# FPGA_01.net
KiCad netlist of a schematic drawn in Altium Designer
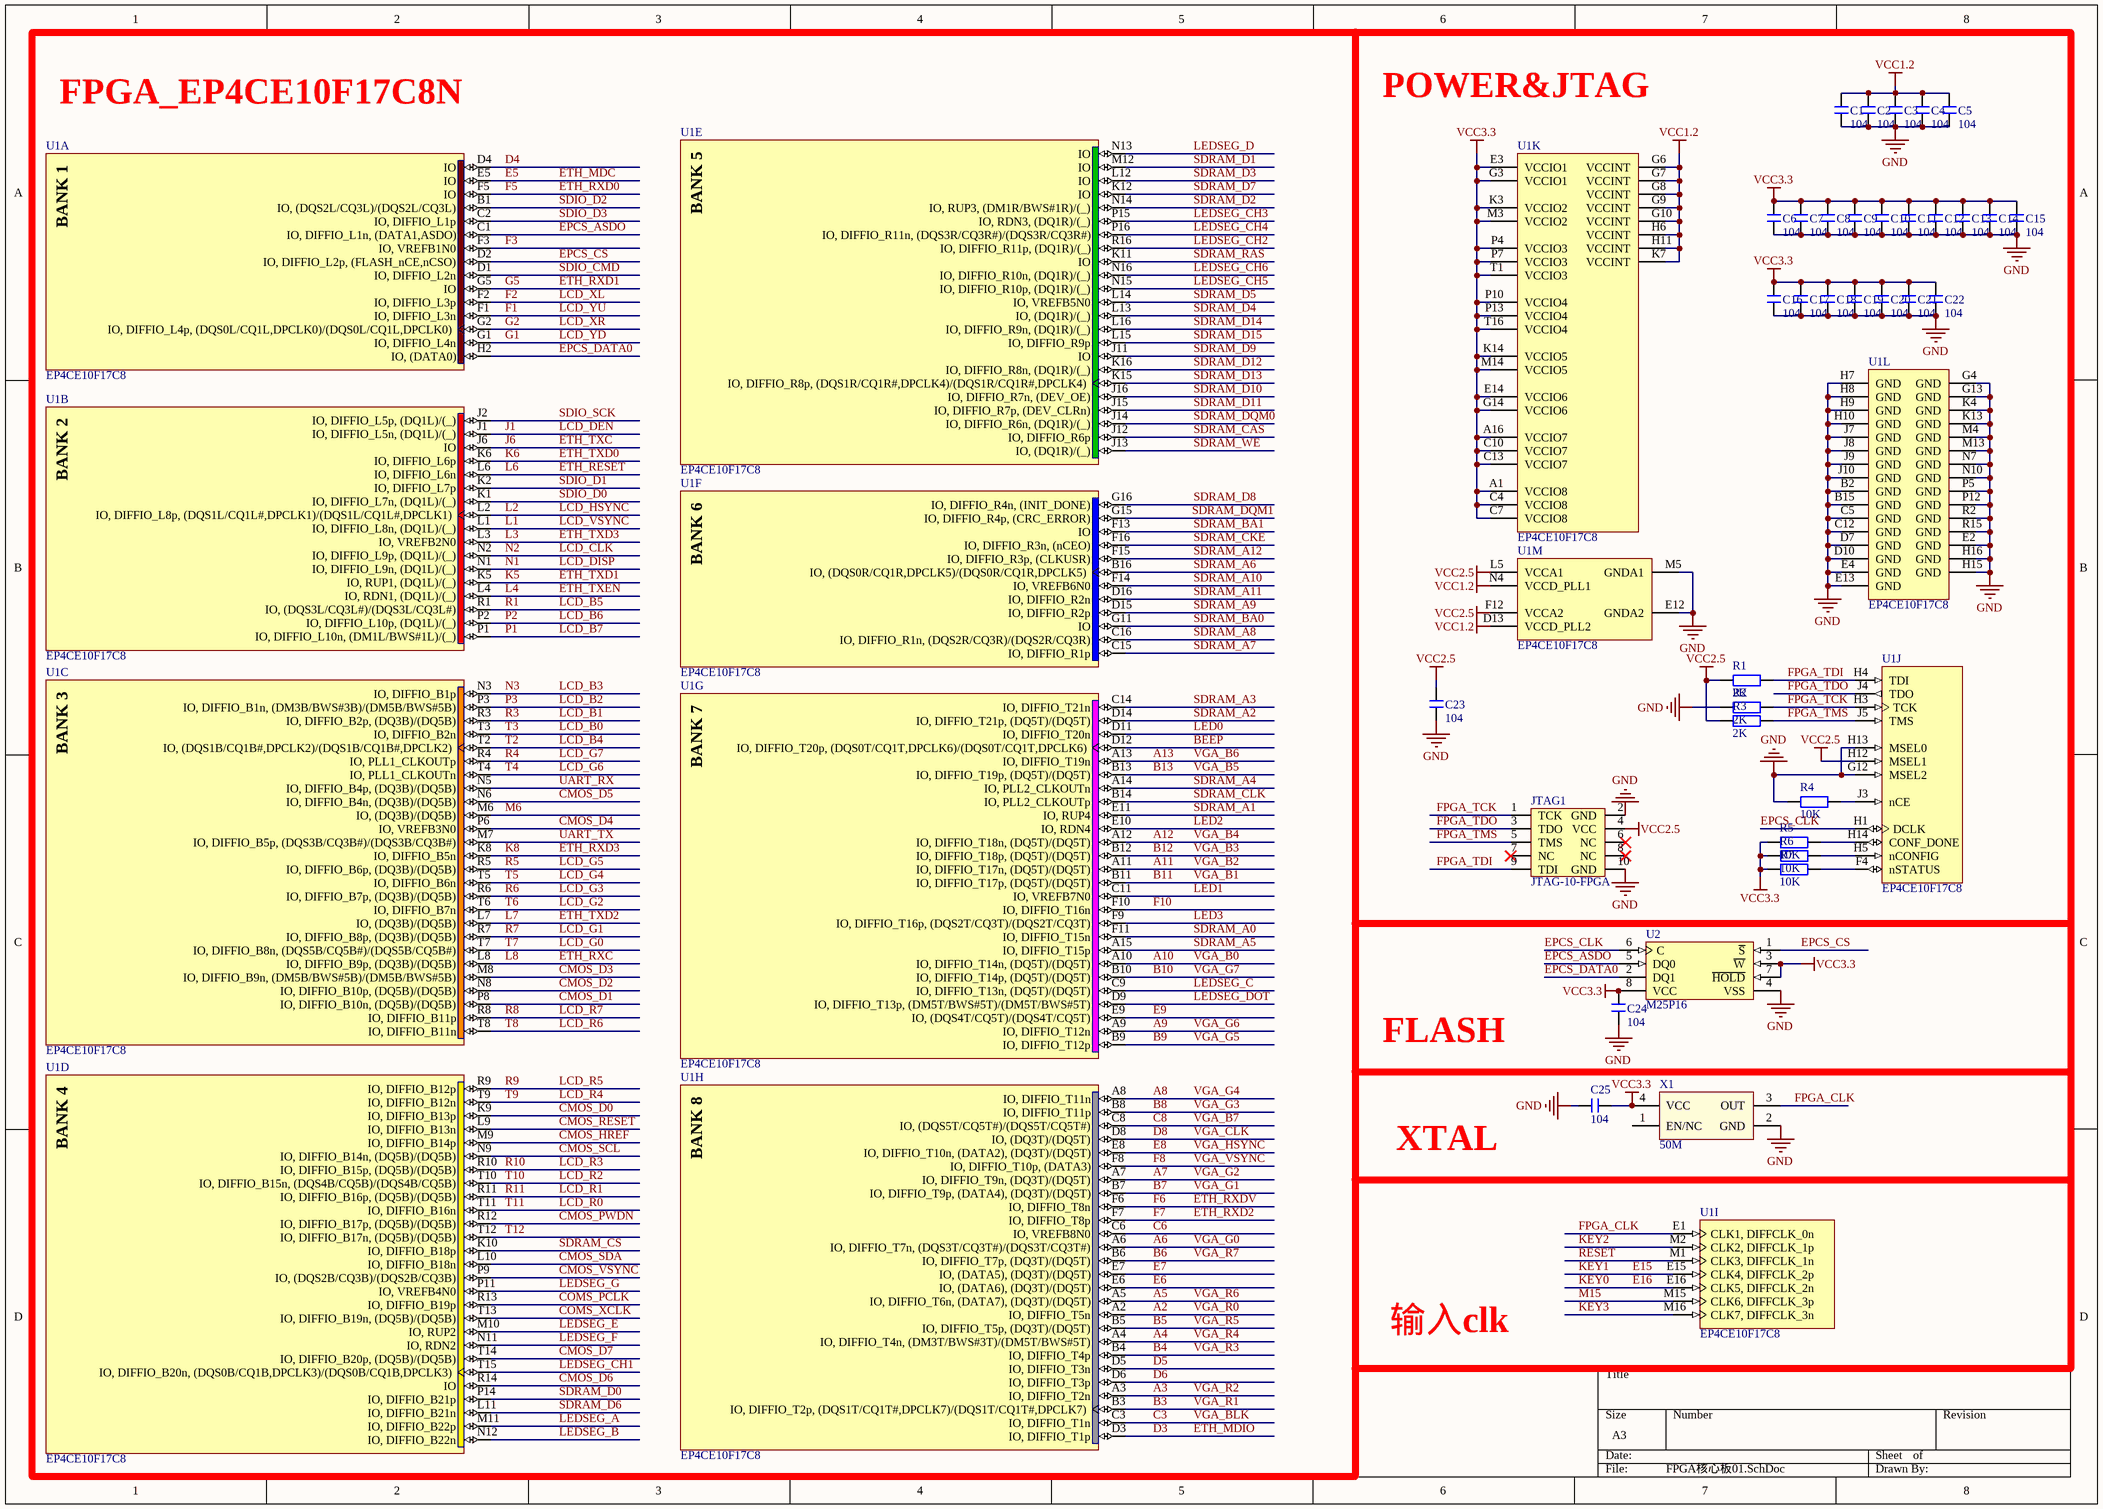
[diagram p0: FPGA核心板01.SchDoc]

(export (version "E")
  (design (tool "Eeschema 10.0.6"))
  (components
    (comp (ref "C1")
      (value "104")
      (footprint "C 0603_L")
      (description "贴片电容")
      (libsource (lib "0.1 - 电阻-电容-电感") (part "C"))
    )
    (comp (ref "C2")
      (value "104")
      (footprint "C 0603_L")
      (description "贴片电容")
      (libsource (lib "0.1 - 电阻-电容-电感") (part "C"))
    )
    (comp (ref "C3")
      (value "104")
      (footprint "C 0603_L")
      (description "贴片电容")
      (libsource (lib "0.1 - 电阻-电容-电感") (part "C"))
    )
    (comp (ref "C4")
      (value "104")
      (footprint "C 0603_L")
      (description "贴片电容")
      (libsource (lib "0.1 - 电阻-电容-电感") (part "C"))
    )
    (comp (ref "C5")
      (value "104")
      (footprint "C 0603_L")
      (description "贴片电容")
      (libsource (lib "0.1 - 电阻-电容-电感") (part "C"))
    )
    (comp (ref "C6")
      (value "104")
      (footprint "C 0603_L")
      (description "贴片电容")
      (libsource (lib "0.1 - 电阻-电容-电感") (part "C"))
    )
    (comp (ref "C7")
      (value "104")
      (footprint "C 0603_L")
      (description "贴片电容")
      (libsource (lib "0.1 - 电阻-电容-电感") (part "C"))
    )
    (comp (ref "C8")
      (value "104")
      (footprint "C 0603_L")
      (description "贴片电容")
      (libsource (lib "0.1 - 电阻-电容-电感") (part "C"))
    )
    (comp (ref "C9")
      (value "104")
      (footprint "C 0603_L")
      (description "贴片电容")
      (libsource (lib "0.1 - 电阻-电容-电感") (part "C"))
    )
    (comp (ref "C10")
      (value "104")
      (footprint "C 0603_L")
      (description "贴片电容")
      (libsource (lib "0.1 - 电阻-电容-电感") (part "C"))
    )
    (comp (ref "C11")
      (value "104")
      (footprint "C 0603_L")
      (description "贴片电容")
      (libsource (lib "0.1 - 电阻-电容-电感") (part "C"))
    )
    (comp (ref "C12")
      (value "104")
      (footprint "C 0603_L")
      (description "贴片电容")
      (libsource (lib "0.1 - 电阻-电容-电感") (part "C"))
    )
    (comp (ref "C13")
      (value "104")
      (footprint "C 0603_L")
      (description "贴片电容")
      (libsource (lib "0.1 - 电阻-电容-电感") (part "C"))
    )
    (comp (ref "C14")
      (value "104")
      (footprint "C 0603_L")
      (description "贴片电容")
      (libsource (lib "0.1 - 电阻-电容-电感") (part "C"))
    )
    (comp (ref "C15")
      (value "104")
      (footprint "C 0603_L")
      (description "贴片电容")
      (libsource (lib "0.1 - 电阻-电容-电感") (part "C"))
    )
    (comp (ref "C16")
      (value "104")
      (footprint "C 0603_L")
      (description "贴片电容")
      (libsource (lib "0.1 - 电阻-电容-电感") (part "C"))
    )
    (comp (ref "C17")
      (value "104")
      (footprint "C 0603_L")
      (description "贴片电容")
      (libsource (lib "0.1 - 电阻-电容-电感") (part "C"))
    )
    (comp (ref "C18")
      (value "104")
      (footprint "C 0603_L")
      (description "贴片电容")
      (libsource (lib "0.1 - 电阻-电容-电感") (part "C"))
    )
    (comp (ref "C19")
      (value "104")
      (footprint "C 0603_L")
      (description "贴片电容")
      (libsource (lib "0.1 - 电阻-电容-电感") (part "C"))
    )
    (comp (ref "C20")
      (value "104")
      (footprint "C 0603_L")
      (description "贴片电容")
      (libsource (lib "0.1 - 电阻-电容-电感") (part "C"))
    )
    (comp (ref "C21")
      (value "104")
      (footprint "C 0603_L")
      (description "贴片电容")
      (libsource (lib "0.1 - 电阻-电容-电感") (part "C"))
    )
    (comp (ref "C22")
      (value "104")
      (footprint "C 0603_L")
      (description "贴片电容")
      (libsource (lib "0.1 - 电阻-电容-电感") (part "C"))
    )
    (comp (ref "C23")
      (value "104")
      (footprint "C 0603_L")
      (description "贴片电容")
      (libsource (lib "0.1 - 电阻-电容-电感") (part "C"))
    )
    (comp (ref "C24")
      (value "104")
      (footprint "C 0603_L")
      (description "贴片电容")
      (libsource (lib "0.1 - 电阻-电容-电感") (part "C"))
    )
    (comp (ref "C25")
      (value "104")
      (footprint "C 0603_L")
      (description "贴片电容")
      (libsource (lib "0.1 - 电阻-电容-电感") (part "C"))
    )
    (comp (ref "JTAG1")
      (value "JTAG-10-FPGA")
      (footprint "JTAG_10_2.54")
      (libsource (lib "PIONEER") (part "JTAG-10-FPGA"))
    )
    (comp (ref "R1")
      (value "2K")
      (footprint "R 0603_L")
      (description "贴片电阻")
      (fields (field (name "版权归属") "来自淘宝 ID：黄晶宝石"))
      (libsource (lib "0.1 - 电阻-电容-电感") (part "R"))
    )
    (comp (ref "R2")
      (value "2K")
      (footprint "R 0603_L")
      (description "贴片电阻")
      (fields (field (name "版权归属") "来自淘宝 ID：黄晶宝石"))
      (libsource (lib "0.1 - 电阻-电容-电感") (part "R"))
    )
    (comp (ref "R3")
      (value "2K")
      (footprint "R 0603_L")
      (description "贴片电阻")
      (fields (field (name "版权归属") "来自淘宝 ID：黄晶宝石"))
      (libsource (lib "0.1 - 电阻-电容-电感") (part "R"))
    )
    (comp (ref "R4")
      (value "10K")
      (footprint "R 0603_L")
      (description "贴片电阻")
      (fields (field (name "版权归属") "来自淘宝 ID：黄晶宝石"))
      (libsource (lib "0.1 - 电阻-电容-电感") (part "R"))
    )
    (comp (ref "R5")
      (value "10K")
      (footprint "R 0603_L")
      (description "贴片电阻")
      (fields (field (name "版权归属") "来自淘宝 ID：黄晶宝石"))
      (libsource (lib "0.1 - 电阻-电容-电感") (part "R"))
    )
    (comp (ref "R6")
      (value "10K")
      (footprint "R 0603_L")
      (description "贴片电阻")
      (fields (field (name "版权归属") "来自淘宝 ID：黄晶宝石"))
      (libsource (lib "0.1 - 电阻-电容-电感") (part "R"))
    )
    (comp (ref "R7")
      (value "10K")
      (footprint "R 0603_L")
      (description "贴片电阻")
      (fields (field (name "版权归属") "来自淘宝 ID：黄晶宝石"))
      (libsource (lib "0.1 - 电阻-电容-电感") (part "R"))
    )
    (comp (ref "U1")
      (value "EP4CE10F17C8")
      (footprint "FBGA256")
      (fields (field (name "PUBLISHER") "Altium Limited"))
      (libsource (lib "PIONEER") (part "EP4CE6F17C8"))
    )
    (comp (ref "U2")
      (value "M25P16")
      (footprint "sop-8")
      (description "16 Mb (x1) Automotive Serial NOR Flash Memory, 75 MHz, 2.7 to 3.6 V, 8-pin SO8")
      (fields (field (name "VOLTAGE") "2.7V-3.6V爭ISHIDDEN=T¦") (field (name "MANUFACTURER") "Micron"))
      (libsource (lib "PIONEER") (part "M25P16"))
    )
    (comp (ref "X1")
      (value "50M")
      (footprint "OSC 3225-4P")
      (description "4脚有源晶振")
      (fields (field (name "版权归属") "源创客"))
      (libsource (lib "2.0 - 保险丝-晶振-光耦") (part "XTAL-ACT-4P"))
    )
  )
  (nets
    (net (code "1") (name "/A2") (class "Default")
      (node (ref "U1") (pin "A2") (pinfunction "IO,_DIFFIO_T5n_A2") (pintype "bidirectional"))
    )
    (net (code "2") (name "/A3") (class "Default")
      (node (ref "U1") (pin "A3") (pinfunction "IO,_DIFFIO_T2n_A3") (pintype "bidirectional"))
    )
    (net (code "3") (name "/A4") (class "Default")
      (node (ref "U1") (pin "A4") (pinfunction "IO,_DIFFIO_T4n,_(DM3T/BWS#3T)/(DM5T/BWS#5T)_A4") (pintype "bidirectional"))
    )
    (net (code "4") (name "/A5") (class "Default")
      (node (ref "U1") (pin "A5") (pinfunction "IO,_DIFFIO_T6n,_(DATA7),_(DQ3T)/(DQ5T)_A5") (pintype "bidirectional"))
    )
    (net (code "5") (name "/A6") (class "Default")
      (node (ref "U1") (pin "A6") (pinfunction "IO,_DIFFIO_T7n,_(DQS3T/CQ3T#)/(DQS3T/CQ3T#)_A6") (pintype "bidirectional"))
    )
    (net (code "6") (name "/A7") (class "Default")
      (node (ref "U1") (pin "A7") (pinfunction "IO,_DIFFIO_T9n,_(DQ3T)/(DQ5T)_A7") (pintype "bidirectional"))
    )
    (net (code "7") (name "/A8") (class "Default")
      (node (ref "U1") (pin "A8") (pinfunction "IO,_DIFFIO_T11n_A8") (pintype "bidirectional"))
    )
    (net (code "8") (name "/A9") (class "Default")
      (node (ref "U1") (pin "A9") (pinfunction "IO,_DIFFIO_T12n_A9") (pintype "bidirectional"))
    )
    (net (code "9") (name "/A10") (class "Default")
      (node (ref "U1") (pin "A10") (pinfunction "IO,_DIFFIO_T14n,_(DQ5T)/(DQ5T)_A10") (pintype "bidirectional"))
    )
    (net (code "10") (name "/A11") (class "Default")
      (node (ref "U1") (pin "A11") (pinfunction "IO,_DIFFIO_T17n,_(DQ5T)/(DQ5T)_A11") (pintype "bidirectional"))
    )
    (net (code "11") (name "/A12") (class "Default")
      (node (ref "U1") (pin "A12") (pinfunction "IO,_DIFFIO_T18n,_(DQ5T)/(DQ5T)_A12") (pintype "bidirectional"))
    )
    (net (code "12") (name "/A13") (class "Default")
      (node (ref "U1") (pin "A13") (pinfunction "IO,_DIFFIO_T19n_A13") (pintype "bidirectional"))
    )
    (net (code "13") (name "/B3") (class "Default")
      (node (ref "U1") (pin "B3") (pinfunction "IO,_DIFFIO_T2p,_(DQS1T/CQ1T#,DPCLK7)/(DQS1T/CQ1T#,DPCLK7)_B3") (pintype "bidirectional"))
    )
    (net (code "14") (name "/B4") (class "Default")
      (node (ref "U1") (pin "B4") (pinfunction "IO,_DIFFIO_T4p_B4") (pintype "bidirectional"))
    )
    (net (code "15") (name "/B5") (class "Default")
      (node (ref "U1") (pin "B5") (pinfunction "IO,_DIFFIO_T5p,_(DQ3T)/(DQ5T)_B5") (pintype "bidirectional"))
    )
    (net (code "16") (name "/B6") (class "Default")
      (node (ref "U1") (pin "B6") (pinfunction "IO,_DIFFIO_T7p,_(DQ3T)/(DQ5T)_B6") (pintype "bidirectional"))
    )
    (net (code "17") (name "/B7") (class "Default")
      (node (ref "U1") (pin "B7") (pinfunction "IO,_DIFFIO_T9p,_(DATA4),_(DQ3T)/(DQ5T)_B7") (pintype "bidirectional"))
    )
    (net (code "18") (name "/B8") (class "Default")
      (node (ref "U1") (pin "B8") (pinfunction "IO,_DIFFIO_T11p_B8") (pintype "bidirectional"))
    )
    (net (code "19") (name "/B9") (class "Default")
      (node (ref "U1") (pin "B9") (pinfunction "IO,_DIFFIO_T12p_B9") (pintype "bidirectional"))
    )
    (net (code "20") (name "/B10") (class "Default")
      (node (ref "U1") (pin "B10") (pinfunction "IO,_DIFFIO_T14p,_(DQ5T)/(DQ5T)_B10") (pintype "bidirectional"))
    )
    (net (code "21") (name "/B11") (class "Default")
      (node (ref "U1") (pin "B11") (pinfunction "IO,_DIFFIO_T17p,_(DQ5T)/(DQ5T)_B11") (pintype "bidirectional"))
    )
    (net (code "22") (name "/B12") (class "Default")
      (node (ref "U1") (pin "B12") (pinfunction "IO,_DIFFIO_T18p,_(DQ5T)/(DQ5T)_B12") (pintype "bidirectional"))
    )
    (net (code "23") (name "/B13") (class "Default")
      (node (ref "U1") (pin "B13") (pinfunction "IO,_DIFFIO_T19p,_(DQ5T)/(DQ5T)_B13") (pintype "bidirectional"))
    )
    (net (code "24") (name "/BEEP") (class "Default")
      (node (ref "U1") (pin "D12") (pinfunction "IO,_DIFFIO_T20p,_(DQS0T/CQ1T,DPCLK6)/(DQS0T/CQ1T,DPCLK6)_D12") (pintype "bidirectional"))
    )
    (net (code "25") (name "/C3") (class "Default")
      (node (ref "U1") (pin "C3") (pinfunction "IO,_DIFFIO_T1n_C3") (pintype "bidirectional"))
    )
    (net (code "26") (name "/C6") (class "Default")
      (node (ref "U1") (pin "C6") (pinfunction "IO,_VREFB8N0_C6") (pintype "bidirectional"))
    )
    (net (code "27") (name "/C8") (class "Default")
      (node (ref "U1") (pin "C8") (pinfunction "IO,_(DQS5T/CQ5T#)/(DQS5T/CQ5T#)_C8") (pintype "bidirectional"))
    )
    (net (code "28") (name "/CMOS_D0") (class "Default")
      (node (ref "U1") (pin "K9") (pinfunction "IO,_DIFFIO_B13p_K9") (pintype "bidirectional"))
    )
    (net (code "29") (name "/CMOS_D1") (class "Default")
      (node (ref "U1") (pin "P8") (pinfunction "IO,_DIFFIO_B10n,_(DQ5B)/(DQ5B)_P8") (pintype "bidirectional"))
    )
    (net (code "30") (name "/CMOS_D2") (class "Default")
      (node (ref "U1") (pin "N8") (pinfunction "IO,_DIFFIO_B10p,_(DQ5B)/(DQ5B)_N8") (pintype "bidirectional"))
    )
    (net (code "31") (name "/CMOS_D3") (class "Default")
      (node (ref "U1") (pin "M8") (pinfunction "IO,_DIFFIO_B9n,_(DM5B/BWS#5B)/(DM5B/BWS#5B)_M8") (pintype "bidirectional"))
    )
    (net (code "32") (name "/CMOS_D4") (class "Default")
      (node (ref "U1") (pin "P6") (pinfunction "IO,_VREFB3N0_P6") (pintype "bidirectional"))
    )
    (net (code "33") (name "/CMOS_D5") (class "Default")
      (node (ref "U1") (pin "N6") (pinfunction "IO,_DIFFIO_B4n,_(DQ3B)/(DQ5B)_N6") (pintype "bidirectional"))
    )
    (net (code "34") (name "/CMOS_D6") (class "Default")
      (node (ref "U1") (pin "R14") (pinfunction "IO_R14") (pintype "bidirectional"))
    )
    (net (code "35") (name "/CMOS_D7") (class "Default")
      (node (ref "U1") (pin "T14") (pinfunction "IO,_DIFFIO_B20p,_(DQ5B)/(DQ5B)_T14") (pintype "bidirectional"))
    )
    (net (code "36") (name "/CMOS_HREF") (class "Default")
      (node (ref "U1") (pin "M9") (pinfunction "IO,_DIFFIO_B14p_M9") (pintype "bidirectional"))
    )
    (net (code "37") (name "/CMOS_PWDN") (class "Default")
      (node (ref "U1") (pin "R12") (pinfunction "IO,_DIFFIO_B17p,_(DQ5B)/(DQ5B)_R12") (pintype "bidirectional"))
    )
    (net (code "38") (name "/CMOS_RESET") (class "Default")
      (node (ref "U1") (pin "L9") (pinfunction "IO,_DIFFIO_B13n_L9") (pintype "bidirectional"))
    )
    (net (code "39") (name "/CMOS_SCL") (class "Default")
      (node (ref "U1") (pin "N9") (pinfunction "IO,_DIFFIO_B14n,_(DQ5B)/(DQ5B)_N9") (pintype "bidirectional"))
    )
    (net (code "40") (name "/CMOS_SDA") (class "Default")
      (node (ref "U1") (pin "L10") (pinfunction "IO,_DIFFIO_B18n_L10") (pintype "bidirectional"))
    )
    (net (code "41") (name "/CMOS_VSYNC") (class "Default")
      (node (ref "U1") (pin "P9") (pinfunction "IO,_(DQS2B/CQ3B)/(DQS2B/CQ3B)_P9") (pintype "bidirectional"))
    )
    (net (code "42") (name "/COMS_PCLK") (class "Default")
      (node (ref "U1") (pin "R13") (pinfunction "IO,_DIFFIO_B19p_R13") (pintype "bidirectional"))
    )
    (net (code "43") (name "/COMS_XCLK") (class "Default")
      (node (ref "U1") (pin "T13") (pinfunction "IO,_DIFFIO_B19n,_(DQ5B)/(DQ5B)_T13") (pintype "bidirectional"))
    )
    (net (code "44") (name "/D3") (class "Default")
      (node (ref "U1") (pin "D3") (pinfunction "IO,_DIFFIO_T1p_D3") (pintype "bidirectional"))
    )
    (net (code "45") (name "/D4") (class "Default")
      (node (ref "U1") (pin "D4") (pinfunction "IO_D4") (pintype "bidirectional"))
    )
    (net (code "46") (name "/D5") (class "Default")
      (node (ref "U1") (pin "D5") (pinfunction "IO,_DIFFIO_T3n_D5") (pintype "bidirectional"))
    )
    (net (code "47") (name "/D6") (class "Default")
      (node (ref "U1") (pin "D6") (pinfunction "IO,_DIFFIO_T3p_D6") (pintype "bidirectional"))
    )
    (net (code "48") (name "/D8") (class "Default")
      (node (ref "U1") (pin "D8") (pinfunction "IO,_(DQ3T)/(DQ5T)_D8") (pintype "bidirectional"))
    )
    (net (code "49") (name "/E5") (class "Default")
      (node (ref "U1") (pin "E5") (pinfunction "IO_E5") (pintype "bidirectional"))
    )
    (net (code "50") (name "/E6") (class "Default")
      (node (ref "U1") (pin "E6") (pinfunction "IO,_(DATA6),_(DQ3T)/(DQ5T)_E6") (pintype "bidirectional"))
    )
    (net (code "51") (name "/E7") (class "Default")
      (node (ref "U1") (pin "E7") (pinfunction "IO,_(DATA5),_(DQ3T)/(DQ5T)_E7") (pintype "bidirectional"))
    )
    (net (code "52") (name "/E8") (class "Default")
      (node (ref "U1") (pin "E8") (pinfunction "IO,_DIFFIO_T10n,_(DATA2),_(DQ3T)/(DQ5T)_E8") (pintype "bidirectional"))
    )
    (net (code "53") (name "/E9") (class "Default")
      (node (ref "U1") (pin "E9") (pinfunction "IO,_(DQS4T/CQ5T)/(DQS4T/CQ5T)_E9") (pintype "bidirectional"))
    )
    (net (code "54") (name "/E15") (class "Default")
      (node (ref "U1") (pin "E15") (pinfunction "CLK4,_DIFFCLK_2p_E15") (pintype "input"))
    )
    (net (code "55") (name "/E16") (class "Default")
      (node (ref "U1") (pin "E16") (pinfunction "CLK5,_DIFFCLK_2n_E16") (pintype "input"))
    )
    (net (code "56") (name "/EPCS_ASDO") (class "Default")
      (node (ref "U1") (pin "C1") (pinfunction "IO,_DIFFIO_L1n,_(DATA1,ASDO)_C1") (pintype "bidirectional"))
      (node (ref "U2") (pin "5") (pinfunction "DQ0_5") (pintype "input"))
    )
    (net (code "57") (name "/EPCS_CLK") (class "Default")
      (node (ref "U1") (pin "H1") (pinfunction "DCLK_H1") (pintype "bidirectional"))
      (node (ref "U2") (pin "6") (pinfunction "C_6") (pintype "input"))
    )
    (net (code "58") (name "/EPCS_CS") (class "Default")
      (node (ref "U1") (pin "D2") (pinfunction "IO,_DIFFIO_L2p,_(FLASH_nCE,nCSO)_D2") (pintype "bidirectional"))
      (node (ref "U2") (pin "1") (pinfunction "~{S}_1") (pintype "input"))
    )
    (net (code "59") (name "/EPCS_DATA0") (class "Default")
      (node (ref "U1") (pin "H2") (pinfunction "IO,_(DATA0)_H2") (pintype "bidirectional"))
      (node (ref "U2") (pin "2") (pinfunction "DQ1_2") (pintype "tri_state"))
    )
    (net (code "60") (name "/ETH_RESET") (class "Default")
      (node (ref "U1") (pin "L6") (pinfunction "IO,_DIFFIO_L6n_L6") (pintype "bidirectional"))
    )
    (net (code "61") (name "/ETH_RXC") (class "Default")
      (node (ref "U1") (pin "L8") (pinfunction "IO,_DIFFIO_B9p,_(DQ3B)/(DQ5B)_L8") (pintype "bidirectional"))
    )
    (net (code "62") (name "/ETH_RXD0") (class "Default")
      (node (ref "U1") (pin "F5") (pinfunction "IO_F5") (pintype "bidirectional"))
    )
    (net (code "63") (name "/ETH_RXD1") (class "Default")
      (node (ref "U1") (pin "G5") (pinfunction "IO_G5") (pintype "bidirectional"))
    )
    (net (code "64") (name "/ETH_RXD2") (class "Default")
      (node (ref "U1") (pin "F7") (pinfunction "IO,_DIFFIO_T8p_F7") (pintype "bidirectional"))
    )
    (net (code "65") (name "/ETH_RXD3") (class "Default")
      (node (ref "U1") (pin "K8") (pinfunction "IO,_DIFFIO_B5n_K8") (pintype "bidirectional"))
    )
    (net (code "66") (name "/ETH_RXDV") (class "Default")
      (node (ref "U1") (pin "F6") (pinfunction "IO,_DIFFIO_T8n_F6") (pintype "bidirectional"))
    )
    (net (code "67") (name "/ETH_TXC") (class "Default")
      (node (ref "U1") (pin "J6") (pinfunction "IO_J6") (pintype "bidirectional"))
    )
    (net (code "68") (name "/ETH_TXD0") (class "Default")
      (node (ref "U1") (pin "K6") (pinfunction "IO,_DIFFIO_L6p_K6") (pintype "bidirectional"))
    )
    (net (code "69") (name "/ETH_TXD1") (class "Default")
      (node (ref "U1") (pin "K5") (pinfunction "IO,_RUP1,_(DQ1L)/(_)_K5") (pintype "bidirectional"))
    )
    (net (code "70") (name "/ETH_TXD2") (class "Default")
      (node (ref "U1") (pin "L7") (pinfunction "IO,_(DQ3B)/(DQ5B)_L7") (pintype "bidirectional"))
    )
    (net (code "71") (name "/ETH_TXD3") (class "Default")
      (node (ref "U1") (pin "L3") (pinfunction "IO,_VREFB2N0_L3") (pintype "bidirectional"))
    )
    (net (code "72") (name "/ETH_TXEN") (class "Default")
      (node (ref "U1") (pin "L4") (pinfunction "IO,_RDN1,_(DQ1L)/(_)_L4") (pintype "bidirectional"))
    )
    (net (code "73") (name "/F1") (class "Default")
      (node (ref "U1") (pin "F1") (pinfunction "IO,_DIFFIO_L3n_F1") (pintype "bidirectional"))
    )
    (net (code "74") (name "/F2") (class "Default")
      (node (ref "U1") (pin "F2") (pinfunction "IO,_DIFFIO_L3p_F2") (pintype "bidirectional"))
    )
    (net (code "75") (name "/F3") (class "Default")
      (node (ref "U1") (pin "F3") (pinfunction "IO,_VREFB1N0_F3") (pintype "bidirectional"))
    )
    (net (code "76") (name "/F8") (class "Default")
      (node (ref "U1") (pin "F8") (pinfunction "IO,_DIFFIO_T10p,_(DATA3)_F8") (pintype "bidirectional"))
    )
    (net (code "77") (name "/F10") (class "Default")
      (node (ref "U1") (pin "F10") (pinfunction "IO,_DIFFIO_T16n_F10") (pintype "bidirectional"))
    )
    (net (code "78") (name "/FPGA_CLK") (class "Default")
      (node (ref "U1") (pin "E1") (pinfunction "CLK1,_DIFFCLK_0n_E1") (pintype "input"))
      (node (ref "X1") (pin "3") (pinfunction "OUT_3") (pintype "passive"))
    )
    (net (code "79") (name "/FPGA_TCK") (class "Default")
      (node (ref "JTAG1") (pin "1") (pinfunction "TCK_1") (pintype "passive"))
      (node (ref "R2") (pin "2") (pinfunction "2_2") (pintype "passive"))
      (node (ref "U1") (pin "H3") (pinfunction "TCK_H3") (pintype "input"))
    )
    (net (code "80") (name "/FPGA_TDI") (class "Default")
      (node (ref "JTAG1") (pin "9") (pinfunction "TDI_9") (pintype "passive"))
      (node (ref "R1") (pin "2") (pinfunction "2_2") (pintype "passive"))
      (node (ref "U1") (pin "H4") (pinfunction "TDI_H4") (pintype "input"))
    )
    (net (code "81") (name "/FPGA_TDO") (class "Default")
      (node (ref "JTAG1") (pin "3") (pinfunction "TDO_3") (pintype "passive"))
      (node (ref "U1") (pin "J4") (pinfunction "TDO_J4") (pintype "output"))
    )
    (net (code "82") (name "/FPGA_TMS") (class "Default")
      (node (ref "JTAG1") (pin "5") (pinfunction "TMS_5") (pintype "passive"))
      (node (ref "R3") (pin "2") (pinfunction "2_2") (pintype "passive"))
      (node (ref "U1") (pin "J5") (pinfunction "TMS_J5") (pintype "input"))
    )
    (net (code "83") (name "/G1") (class "Default")
      (node (ref "U1") (pin "G1") (pinfunction "IO,_DIFFIO_L4n_G1") (pintype "bidirectional"))
    )
    (net (code "84") (name "/G2") (class "Default")
      (node (ref "U1") (pin "G2") (pinfunction "IO,_DIFFIO_L4p,_(DQS0L/CQ1L,DPCLK0)/(DQS0L/CQ1L,DPCLK0)_G2") (pintype "bidirectional"))
    )
    (net (code "85") (name "/J1") (class "Default")
      (node (ref "U1") (pin "J1") (pinfunction "IO,_DIFFIO_L5n,_(DQ1L)/(_)_J1") (pintype "bidirectional"))
    )
    (net (code "86") (name "/KEY2") (class "Default")
      (node (ref "U1") (pin "M2") (pinfunction "CLK2,_DIFFCLK_1p_M2") (pintype "input"))
    )
    (net (code "87") (name "/KEY3") (class "Default")
      (node (ref "U1") (pin "M16") (pinfunction "CLK7,_DIFFCLK_3n_M16") (pintype "input"))
    )
    (net (code "88") (name "/L1") (class "Default")
      (node (ref "U1") (pin "L1") (pinfunction "IO,_DIFFIO_L8n,_(DQ1L)/(_)_L1") (pintype "bidirectional"))
    )
    (net (code "89") (name "/L2") (class "Default")
      (node (ref "U1") (pin "L2") (pinfunction "IO,_DIFFIO_L8p,_(DQS1L/CQ1L#,DPCLK1)/(DQS1L/CQ1L#,DPCLK1)_L2") (pintype "bidirectional"))
    )
    (net (code "90") (name "/LCD_B0") (class "Default")
      (node (ref "U1") (pin "T3") (pinfunction "IO,_DIFFIO_B2n_T3") (pintype "bidirectional"))
    )
    (net (code "91") (name "/LCD_B1") (class "Default")
      (node (ref "U1") (pin "R3") (pinfunction "IO,_DIFFIO_B2p,_(DQ3B)/(DQ5B)_R3") (pintype "bidirectional"))
    )
    (net (code "92") (name "/LCD_B2") (class "Default")
      (node (ref "U1") (pin "P3") (pinfunction "IO,_DIFFIO_B1n,_(DM3B/BWS#3B)/(DM5B/BWS#5B)_P3") (pintype "bidirectional"))
    )
    (net (code "93") (name "/LCD_B3") (class "Default")
      (node (ref "U1") (pin "N3") (pinfunction "IO,_DIFFIO_B1p_N3") (pintype "bidirectional"))
    )
    (net (code "94") (name "/LCD_B4") (class "Default")
      (node (ref "U1") (pin "T2") (pinfunction "IO,_(DQS1B/CQ1B#,DPCLK2)/(DQS1B/CQ1B#,DPCLK2)_T2") (pintype "bidirectional"))
    )
    (net (code "95") (name "/LCD_B5") (class "Default")
      (node (ref "U1") (pin "R1") (pinfunction "IO,_(DQS3L/CQ3L#)/(DQS3L/CQ3L#)_R1") (pintype "bidirectional"))
    )
    (net (code "96") (name "/LCD_B6") (class "Default")
      (node (ref "U1") (pin "P2") (pinfunction "IO,_DIFFIO_L10p,_(DQ1L)/(_)_P2") (pintype "bidirectional"))
    )
    (net (code "97") (name "/LCD_B7") (class "Default")
      (node (ref "U1") (pin "P1") (pinfunction "IO,_DIFFIO_L10n,_(DM1L/BWS#1L)/(_)_P1") (pintype "bidirectional"))
    )
    (net (code "98") (name "/LCD_CLK") (class "Default")
      (node (ref "U1") (pin "N2") (pinfunction "IO,_DIFFIO_L9p,_(DQ1L)/(_)_N2") (pintype "bidirectional"))
    )
    (net (code "99") (name "/LCD_DISP") (class "Default")
      (node (ref "U1") (pin "N1") (pinfunction "IO,_DIFFIO_L9n,_(DQ1L)/(_)_N1") (pintype "bidirectional"))
    )
    (net (code "100") (name "/LCD_G0") (class "Default")
      (node (ref "U1") (pin "T7") (pinfunction "IO,_DIFFIO_B8n,_(DQS5B/CQ5B#)/(DQS5B/CQ5B#)_T7") (pintype "bidirectional"))
    )
    (net (code "101") (name "/LCD_G1") (class "Default")
      (node (ref "U1") (pin "R7") (pinfunction "IO,_DIFFIO_B8p,_(DQ3B)/(DQ5B)_R7") (pintype "bidirectional"))
    )
    (net (code "102") (name "/LCD_G2") (class "Default")
      (node (ref "U1") (pin "T6") (pinfunction "IO,_DIFFIO_B7n_T6") (pintype "bidirectional"))
    )
    (net (code "103") (name "/LCD_G3") (class "Default")
      (node (ref "U1") (pin "R6") (pinfunction "IO,_DIFFIO_B7p,_(DQ3B)/(DQ5B)_R6") (pintype "bidirectional"))
    )
    (net (code "104") (name "/LCD_G4") (class "Default")
      (node (ref "U1") (pin "T5") (pinfunction "IO,_DIFFIO_B6n_T5") (pintype "bidirectional"))
    )
    (net (code "105") (name "/LCD_G5") (class "Default")
      (node (ref "U1") (pin "R5") (pinfunction "IO,_DIFFIO_B6p,_(DQ3B)/(DQ5B)_R5") (pintype "bidirectional"))
    )
    (net (code "106") (name "/LCD_G6") (class "Default")
      (node (ref "U1") (pin "T4") (pinfunction "IO,_PLL1_CLKOUTn_T4") (pintype "bidirectional"))
    )
    (net (code "107") (name "/LCD_G7") (class "Default")
      (node (ref "U1") (pin "R4") (pinfunction "IO,_PLL1_CLKOUTp_R4") (pintype "bidirectional"))
    )
    (net (code "108") (name "/LCD_R0") (class "Default")
      (node (ref "U1") (pin "T11") (pinfunction "IO,_DIFFIO_B16n_T11") (pintype "bidirectional"))
    )
    (net (code "109") (name "/LCD_R1") (class "Default")
      (node (ref "U1") (pin "R11") (pinfunction "IO,_DIFFIO_B16p,_(DQ5B)/(DQ5B)_R11") (pintype "bidirectional"))
    )
    (net (code "110") (name "/LCD_R2") (class "Default")
      (node (ref "U1") (pin "T10") (pinfunction "IO,_DIFFIO_B15n,_(DQS4B/CQ5B)/(DQS4B/CQ5B)_T10") (pintype "bidirectional"))
    )
    (net (code "111") (name "/LCD_R3") (class "Default")
      (node (ref "U1") (pin "R10") (pinfunction "IO,_DIFFIO_B15p,_(DQ5B)/(DQ5B)_R10") (pintype "bidirectional"))
    )
    (net (code "112") (name "/LCD_R4") (class "Default")
      (node (ref "U1") (pin "T9") (pinfunction "IO,_DIFFIO_B12n_T9") (pintype "bidirectional"))
    )
    (net (code "113") (name "/LCD_R5") (class "Default")
      (node (ref "U1") (pin "R9") (pinfunction "IO,_DIFFIO_B12p_R9") (pintype "bidirectional"))
    )
    (net (code "114") (name "/LCD_R6") (class "Default")
      (node (ref "U1") (pin "T8") (pinfunction "IO,_DIFFIO_B11n_T8") (pintype "bidirectional"))
    )
    (net (code "115") (name "/LCD_R7") (class "Default")
      (node (ref "U1") (pin "R8") (pinfunction "IO,_DIFFIO_B11p_R8") (pintype "bidirectional"))
    )
    (net (code "116") (name "/LED0") (class "Default")
      (node (ref "U1") (pin "D11") (pinfunction "IO,_DIFFIO_T20n_D11") (pintype "bidirectional"))
    )
    (net (code "117") (name "/LED1") (class "Default")
      (node (ref "U1") (pin "C11") (pinfunction "IO,_VREFB7N0_C11") (pintype "bidirectional"))
    )
    (net (code "118") (name "/LED2") (class "Default")
      (node (ref "U1") (pin "E10") (pinfunction "IO,_RDN4_E10") (pintype "bidirectional"))
    )
    (net (code "119") (name "/LED3") (class "Default")
      (node (ref "U1") (pin "F9") (pinfunction "IO,_DIFFIO_T16p,_(DQS2T/CQ3T)/(DQS2T/CQ3T)_F9") (pintype "bidirectional"))
    )
    (net (code "120") (name "/LEDSEG_A") (class "Default")
      (node (ref "U1") (pin "M11") (pinfunction "IO,_DIFFIO_B22p_M11") (pintype "bidirectional"))
    )
    (net (code "121") (name "/LEDSEG_B") (class "Default")
      (node (ref "U1") (pin "N12") (pinfunction "IO,_DIFFIO_B22n_N12") (pintype "bidirectional"))
    )
    (net (code "122") (name "/LEDSEG_C") (class "Default")
      (node (ref "U1") (pin "C9") (pinfunction "IO,_DIFFIO_T13n,_(DQ5T)/(DQ5T)_C9") (pintype "bidirectional"))
    )
    (net (code "123") (name "/LEDSEG_CH1") (class "Default")
      (node (ref "U1") (pin "T15") (pinfunction "IO,_DIFFIO_B20n,_(DQS0B/CQ1B,DPCLK3)/(DQS0B/CQ1B,DPCLK3)_T15") (pintype "bidirectional"))
    )
    (net (code "124") (name "/LEDSEG_CH2") (class "Default")
      (node (ref "U1") (pin "R16") (pinfunction "IO,_DIFFIO_R11p,_(DQ1R)/(_)_R16") (pintype "bidirectional"))
    )
    (net (code "125") (name "/LEDSEG_CH3") (class "Default")
      (node (ref "U1") (pin "P15") (pinfunction "IO,_RDN3,_(DQ1R)/(_)_P15") (pintype "bidirectional"))
    )
    (net (code "126") (name "/LEDSEG_CH4") (class "Default")
      (node (ref "U1") (pin "P16") (pinfunction "IO,_DIFFIO_R11n,_(DQS3R/CQ3R#)/(DQS3R/CQ3R#)_P16") (pintype "bidirectional"))
    )
    (net (code "127") (name "/LEDSEG_CH5") (class "Default")
      (node (ref "U1") (pin "N15") (pinfunction "IO,_DIFFIO_R10p,_(DQ1R)/(_)_N15") (pintype "bidirectional"))
    )
    (net (code "128") (name "/LEDSEG_CH6") (class "Default")
      (node (ref "U1") (pin "N16") (pinfunction "IO,_DIFFIO_R10n,_(DQ1R)/(_)_N16") (pintype "bidirectional"))
    )
    (net (code "129") (name "/LEDSEG_D") (class "Default")
      (node (ref "U1") (pin "N13") (pinfunction "IO_N13") (pintype "bidirectional"))
    )
    (net (code "130") (name "/LEDSEG_DOT") (class "Default")
      (node (ref "U1") (pin "D9") (pinfunction "IO,_DIFFIO_T13p,_(DM5T/BWS#5T)/(DM5T/BWS#5T)_D9") (pintype "bidirectional"))
    )
    (net (code "131") (name "/LEDSEG_E") (class "Default")
      (node (ref "U1") (pin "M10") (pinfunction "IO,_RUP2_M10") (pintype "bidirectional"))
    )
    (net (code "132") (name "/LEDSEG_F") (class "Default")
      (node (ref "U1") (pin "N11") (pinfunction "IO,_RDN2_N11") (pintype "bidirectional"))
    )
    (net (code "133") (name "/LEDSEG_G") (class "Default")
      (node (ref "U1") (pin "P11") (pinfunction "IO,_VREFB4N0_P11") (pintype "bidirectional"))
    )
    (net (code "134") (name "/M6") (class "Default")
      (node (ref "U1") (pin "M6") (pinfunction "IO,_(DQ3B)/(DQ5B)_M6") (pintype "bidirectional"))
    )
    (net (code "135") (name "/M15") (class "Default")
      (node (ref "U1") (pin "M15") (pinfunction "CLK6,_DIFFCLK_3p_M15") (pintype "input"))
    )
    (net (code "136") (name "/RESET") (class "Default")
      (node (ref "U1") (pin "M1") (pinfunction "CLK3,_DIFFCLK_1n_M1") (pintype "input"))
    )
    (net (code "137") (name "/SDIO_CMD") (class "Default")
      (node (ref "U1") (pin "D1") (pinfunction "IO,_DIFFIO_L2n_D1") (pintype "bidirectional"))
    )
    (net (code "138") (name "/SDIO_D0") (class "Default")
      (node (ref "U1") (pin "K1") (pinfunction "IO,_DIFFIO_L7n,_(DQ1L)/(_)_K1") (pintype "bidirectional"))
    )
    (net (code "139") (name "/SDIO_D1") (class "Default")
      (node (ref "U1") (pin "K2") (pinfunction "IO,_DIFFIO_L7p_K2") (pintype "bidirectional"))
    )
    (net (code "140") (name "/SDIO_D2") (class "Default")
      (node (ref "U1") (pin "B1") (pinfunction "IO,_(DQS2L/CQ3L)/(DQS2L/CQ3L)_B1") (pintype "bidirectional"))
    )
    (net (code "141") (name "/SDIO_D3") (class "Default")
      (node (ref "U1") (pin "C2") (pinfunction "IO,_DIFFIO_L1p_C2") (pintype "bidirectional"))
    )
    (net (code "142") (name "/SDIO_SCK") (class "Default")
      (node (ref "U1") (pin "J2") (pinfunction "IO,_DIFFIO_L5p,_(DQ1L)/(_)_J2") (pintype "bidirectional"))
    )
    (net (code "143") (name "/SDRAM_A0") (class "Default")
      (node (ref "U1") (pin "F11") (pinfunction "IO,_DIFFIO_T15n_F11") (pintype "bidirectional"))
    )
    (net (code "144") (name "/SDRAM_A1") (class "Default")
      (node (ref "U1") (pin "E11") (pinfunction "IO,_RUP4_E11") (pintype "bidirectional"))
    )
    (net (code "145") (name "/SDRAM_A2") (class "Default")
      (node (ref "U1") (pin "D14") (pinfunction "IO,_DIFFIO_T21p,_(DQ5T)/(DQ5T)_D14") (pintype "bidirectional"))
    )
    (net (code "146") (name "/SDRAM_A3") (class "Default")
      (node (ref "U1") (pin "C14") (pinfunction "IO,_DIFFIO_T21n_C14") (pintype "bidirectional"))
    )
    (net (code "147") (name "/SDRAM_A4") (class "Default")
      (node (ref "U1") (pin "A14") (pinfunction "IO,_PLL2_CLKOUTn_A14") (pintype "bidirectional"))
    )
    (net (code "148") (name "/SDRAM_A5") (class "Default")
      (node (ref "U1") (pin "A15") (pinfunction "IO,_DIFFIO_T15p_A15") (pintype "bidirectional"))
    )
    (net (code "149") (name "/SDRAM_A6") (class "Default")
      (node (ref "U1") (pin "B16") (pinfunction "IO,_(DQS0R/CQ1R,DPCLK5)/(DQS0R/CQ1R,DPCLK5)_B16") (pintype "bidirectional"))
    )
    (net (code "150") (name "/SDRAM_A7") (class "Default")
      (node (ref "U1") (pin "C15") (pinfunction "IO,_DIFFIO_R1p_C15") (pintype "bidirectional"))
    )
    (net (code "151") (name "/SDRAM_A8") (class "Default")
      (node (ref "U1") (pin "C16") (pinfunction "IO,_DIFFIO_R1n,_(DQS2R/CQ3R)/(DQS2R/CQ3R)_C16") (pintype "bidirectional"))
    )
    (net (code "152") (name "/SDRAM_A9") (class "Default")
      (node (ref "U1") (pin "D15") (pinfunction "IO,_DIFFIO_R2p_D15") (pintype "bidirectional"))
    )
    (net (code "153") (name "/SDRAM_A10") (class "Default")
      (node (ref "U1") (pin "F14") (pinfunction "IO,_VREFB6N0_F14") (pintype "bidirectional"))
    )
    (net (code "154") (name "/SDRAM_A11") (class "Default")
      (node (ref "U1") (pin "D16") (pinfunction "IO,_DIFFIO_R2n_D16") (pintype "bidirectional"))
    )
    (net (code "155") (name "/SDRAM_A12") (class "Default")
      (node (ref "U1") (pin "F15") (pinfunction "IO,_DIFFIO_R3p,_(CLKUSR)_F15") (pintype "bidirectional"))
    )
    (net (code "156") (name "/SDRAM_BA0") (class "Default")
      (node (ref "U1") (pin "G11") (pinfunction "IO_G11") (pintype "bidirectional"))
    )
    (net (code "157") (name "/SDRAM_BA1") (class "Default")
      (node (ref "U1") (pin "F13") (pinfunction "IO_F13") (pintype "bidirectional"))
    )
    (net (code "158") (name "/SDRAM_CAS") (class "Default")
      (node (ref "U1") (pin "J12") (pinfunction "IO,_DIFFIO_R6p_J12") (pintype "bidirectional"))
    )
    (net (code "159") (name "/SDRAM_CKE") (class "Default")
      (node (ref "U1") (pin "F16") (pinfunction "IO,_DIFFIO_R3n,_(nCEO)_F16") (pintype "bidirectional"))
    )
    (net (code "160") (name "/SDRAM_CLK") (class "Default")
      (node (ref "U1") (pin "B14") (pinfunction "IO,_PLL2_CLKOUTp_B14") (pintype "bidirectional"))
    )
    (net (code "161") (name "/SDRAM_CS") (class "Default")
      (node (ref "U1") (pin "K10") (pinfunction "IO,_DIFFIO_B18p_K10") (pintype "bidirectional"))
    )
    (net (code "162") (name "/SDRAM_D0") (class "Default")
      (node (ref "U1") (pin "P14") (pinfunction "IO,_DIFFIO_B21p_P14") (pintype "bidirectional"))
    )
    (net (code "163") (name "/SDRAM_D1") (class "Default")
      (node (ref "U1") (pin "M12") (pinfunction "IO_M12") (pintype "bidirectional"))
    )
    (net (code "164") (name "/SDRAM_D2") (class "Default")
      (node (ref "U1") (pin "N14") (pinfunction "IO,_RUP3,_(DM1R/BWS#1R)/(_)_N14") (pintype "bidirectional"))
    )
    (net (code "165") (name "/SDRAM_D3") (class "Default")
      (node (ref "U1") (pin "L12") (pinfunction "IO_L12") (pintype "bidirectional"))
    )
    (net (code "166") (name "/SDRAM_D4") (class "Default")
      (node (ref "U1") (pin "L13") (pinfunction "IO,_(DQ1R)/(_)_L13") (pintype "bidirectional"))
    )
    (net (code "167") (name "/SDRAM_D5") (class "Default")
      (node (ref "U1") (pin "L14") (pinfunction "IO,_VREFB5N0_L14") (pintype "bidirectional"))
    )
    (net (code "168") (name "/SDRAM_D6") (class "Default")
      (node (ref "U1") (pin "L11") (pinfunction "IO,_DIFFIO_B21n_L11") (pintype "bidirectional"))
    )
    (net (code "169") (name "/SDRAM_D7") (class "Default")
      (node (ref "U1") (pin "K12") (pinfunction "IO_K12") (pintype "bidirectional"))
    )
    (net (code "170") (name "/SDRAM_D8") (class "Default")
      (node (ref "U1") (pin "G16") (pinfunction "IO,_DIFFIO_R4n,_(INIT_DONE)_G16") (pintype "bidirectional"))
    )
    (net (code "171") (name "/SDRAM_D9") (class "Default")
      (node (ref "U1") (pin "J11") (pinfunction "IO_J11") (pintype "bidirectional"))
    )
    (net (code "172") (name "/SDRAM_D10") (class "Default")
      (node (ref "U1") (pin "J16") (pinfunction "IO,_DIFFIO_R7n,_(DEV_OE)_J16") (pintype "bidirectional"))
    )
    (net (code "173") (name "/SDRAM_D11") (class "Default")
      (node (ref "U1") (pin "J15") (pinfunction "IO,_DIFFIO_R7p,_(DEV_CLRn)_J15") (pintype "bidirectional"))
    )
    (net (code "174") (name "/SDRAM_D12") (class "Default")
      (node (ref "U1") (pin "K16") (pinfunction "IO,_DIFFIO_R8n,_(DQ1R)/(_)_K16") (pintype "bidirectional"))
    )
    (net (code "175") (name "/SDRAM_D13") (class "Default")
      (node (ref "U1") (pin "K15") (pinfunction "IO,_DIFFIO_R8p,_(DQS1R/CQ1R#,DPCLK4)/(DQS1R/CQ1R#,DPCLK4)_K15") (pintype "bidirectional"))
    )
    (net (code "176") (name "/SDRAM_D14") (class "Default")
      (node (ref "U1") (pin "L16") (pinfunction "IO,_DIFFIO_R9n,_(DQ1R)/(_)_L16") (pintype "bidirectional"))
    )
    (net (code "177") (name "/SDRAM_D15") (class "Default")
      (node (ref "U1") (pin "L15") (pinfunction "IO,_DIFFIO_R9p_L15") (pintype "bidirectional"))
    )
    (net (code "178") (name "/SDRAM_DQM0") (class "Default")
      (node (ref "U1") (pin "J14") (pinfunction "IO,_DIFFIO_R6n,_(DQ1R)/(_)_J14") (pintype "bidirectional"))
    )
    (net (code "179") (name "/SDRAM_DQM1") (class "Default")
      (node (ref "U1") (pin "G15") (pinfunction "IO,_DIFFIO_R4p,_(CRC_ERROR)_G15") (pintype "bidirectional"))
    )
    (net (code "180") (name "/SDRAM_RAS") (class "Default")
      (node (ref "U1") (pin "K11") (pinfunction "IO_K11") (pintype "bidirectional"))
    )
    (net (code "181") (name "/SDRAM_WE") (class "Default")
      (node (ref "U1") (pin "J13") (pinfunction "IO,_(DQ1R)/(_)_J13") (pintype "bidirectional"))
    )
    (net (code "182") (name "/T12") (class "Default")
      (node (ref "U1") (pin "T12") (pinfunction "IO,_DIFFIO_B17n,_(DQ5B)/(DQ5B)_T12") (pintype "bidirectional"))
    )
    (net (code "183") (name "/UART_RX") (class "Default")
      (node (ref "U1") (pin "N5") (pinfunction "IO,_DIFFIO_B4p,_(DQ3B)/(DQ5B)_N5") (pintype "bidirectional"))
    )
    (net (code "184") (name "/UART_TX") (class "Default")
      (node (ref "U1") (pin "M7") (pinfunction "IO,_DIFFIO_B5p,_(DQS3B/CQ3B#)/(DQS3B/CQ3B#)_M7") (pintype "bidirectional"))
    )
    (net (code "185") (name "GND") (class "Default")
      (node (ref "C1") (pin "1") (pinfunction "1_1") (pintype "passive"))
      (node (ref "C10") (pin "1") (pinfunction "1_1") (pintype "passive"))
      (node (ref "C11") (pin "1") (pinfunction "1_1") (pintype "passive"))
      (node (ref "C12") (pin "1") (pinfunction "1_1") (pintype "passive"))
      (node (ref "C13") (pin "1") (pinfunction "1_1") (pintype "passive"))
      (node (ref "C14") (pin "1") (pinfunction "1_1") (pintype "passive"))
      (node (ref "C15") (pin "1") (pinfunction "1_1") (pintype "passive"))
      (node (ref "C16") (pin "1") (pinfunction "1_1") (pintype "passive"))
      (node (ref "C17") (pin "1") (pinfunction "1_1") (pintype "passive"))
      (node (ref "C18") (pin "1") (pinfunction "1_1") (pintype "passive"))
      (node (ref "C19") (pin "1") (pinfunction "1_1") (pintype "passive"))
      (node (ref "C2") (pin "1") (pinfunction "1_1") (pintype "passive"))
      (node (ref "C20") (pin "1") (pinfunction "1_1") (pintype "passive"))
      (node (ref "C21") (pin "1") (pinfunction "1_1") (pintype "passive"))
      (node (ref "C22") (pin "1") (pinfunction "1_1") (pintype "passive"))
      (node (ref "C23") (pin "1") (pinfunction "1_1") (pintype "passive"))
      (node (ref "C24") (pin "1") (pinfunction "1_1") (pintype "passive"))
      (node (ref "C25") (pin "2") (pinfunction "2_2") (pintype "passive"))
      (node (ref "C3") (pin "1") (pinfunction "1_1") (pintype "passive"))
      (node (ref "C4") (pin "1") (pinfunction "1_1") (pintype "passive"))
      (node (ref "C5") (pin "1") (pinfunction "1_1") (pintype "passive"))
      (node (ref "C6") (pin "1") (pinfunction "1_1") (pintype "passive"))
      (node (ref "C7") (pin "1") (pinfunction "1_1") (pintype "passive"))
      (node (ref "C8") (pin "1") (pinfunction "1_1") (pintype "passive"))
      (node (ref "C9") (pin "1") (pinfunction "1_1") (pintype "passive"))
      (node (ref "JTAG1") (pin "10") (pinfunction "GND_10") (pintype "passive"))
      (node (ref "JTAG1") (pin "2") (pinfunction "GND_2") (pintype "passive"))
      (node (ref "R2") (pin "1") (pinfunction "1_1") (pintype "passive"))
      (node (ref "R4") (pin "1") (pinfunction "1_1") (pintype "passive"))
      (node (ref "U1") (pin "B15") (pinfunction "GND_B15") (pintype "power_in"))
      (node (ref "U1") (pin "B2") (pinfunction "GND_B2") (pintype "power_in"))
      (node (ref "U1") (pin "C12") (pinfunction "GND_C12") (pintype "power_in"))
      (node (ref "U1") (pin "C5") (pinfunction "GND_C5") (pintype "power_in"))
      (node (ref "U1") (pin "D10") (pinfunction "GND_D10") (pintype "power_in"))
      (node (ref "U1") (pin "D7") (pinfunction "GND_D7") (pintype "power_in"))
      (node (ref "U1") (pin "E12") (pinfunction "GNDA2_E12") (pintype "power_in"))
      (node (ref "U1") (pin "E13") (pinfunction "GND_E13") (pintype "power_in"))
      (node (ref "U1") (pin "E2") (pinfunction "GND_E2") (pintype "power_in"))
      (node (ref "U1") (pin "E4") (pinfunction "GND_E4") (pintype "power_in"))
      (node (ref "U1") (pin "G12") (pinfunction "MSEL2_G12") (pintype "input"))
      (node (ref "U1") (pin "G13") (pinfunction "GND_G13") (pintype "power_in"))
      (node (ref "U1") (pin "G4") (pinfunction "GND_G4") (pintype "power_in"))
      (node (ref "U1") (pin "H10") (pinfunction "GND_H10") (pintype "power_in"))
      (node (ref "U1") (pin "H13") (pinfunction "MSEL0_H13") (pintype "input"))
      (node (ref "U1") (pin "H15") (pinfunction "GND_H15") (pintype "power_in"))
      (node (ref "U1") (pin "H16") (pinfunction "GND_H16") (pintype "power_in"))
      (node (ref "U1") (pin "H7") (pinfunction "GND_H7") (pintype "power_in"))
      (node (ref "U1") (pin "H8") (pinfunction "GND_H8") (pintype "power_in"))
      (node (ref "U1") (pin "H9") (pinfunction "GND_H9") (pintype "power_in"))
      (node (ref "U1") (pin "J10") (pinfunction "GND_J10") (pintype "power_in"))
      (node (ref "U1") (pin "J7") (pinfunction "GND_J7") (pintype "power_in"))
      (node (ref "U1") (pin "J8") (pinfunction "GND_J8") (pintype "power_in"))
      (node (ref "U1") (pin "J9") (pinfunction "GND_J9") (pintype "power_in"))
      (node (ref "U1") (pin "K13") (pinfunction "GND_K13") (pintype "power_in"))
      (node (ref "U1") (pin "K4") (pinfunction "GND_K4") (pintype "power_in"))
      (node (ref "U1") (pin "M13") (pinfunction "GND_M13") (pintype "power_in"))
      (node (ref "U1") (pin "M4") (pinfunction "GND_M4") (pintype "power_in"))
      (node (ref "U1") (pin "M5") (pinfunction "GNDA1_M5") (pintype "power_in"))
      (node (ref "U1") (pin "N10") (pinfunction "GND_N10") (pintype "power_in"))
      (node (ref "U1") (pin "N7") (pinfunction "GND_N7") (pintype "power_in"))
      (node (ref "U1") (pin "P12") (pinfunction "GND_P12") (pintype "power_in"))
      (node (ref "U1") (pin "P5") (pinfunction "GND_P5") (pintype "power_in"))
      (node (ref "U1") (pin "R15") (pinfunction "GND_R15") (pintype "power_in"))
      (node (ref "U1") (pin "R2") (pinfunction "GND_R2") (pintype "power_in"))
      (node (ref "U2") (pin "4") (pinfunction "VSS_4") (pintype "power_in"))
      (node (ref "X1") (pin "2") (pinfunction "GND_2") (pintype "passive"))
    )
    (net (code "186") (name "Net-(U1J-CONF_DONE)") (class "Default")
      (node (ref "R5") (pin "2") (pinfunction "2_2") (pintype "passive"))
      (node (ref "U1") (pin "H14") (pinfunction "CONF_DONE_H14") (pintype "bidirectional"))
    )
    (net (code "187") (name "Net-(U1J-nCE)") (class "Default")
      (node (ref "R4") (pin "2") (pinfunction "2_2") (pintype "passive"))
      (node (ref "U1") (pin "J3") (pinfunction "nCE_J3") (pintype "input"))
    )
    (net (code "188") (name "Net-(U1J-nCONFIG)") (class "Default")
      (node (ref "R6") (pin "2") (pinfunction "2_2") (pintype "passive"))
      (node (ref "U1") (pin "H5") (pinfunction "nCONFIG_H5") (pintype "input"))
    )
    (net (code "189") (name "Net-(U1J-nSTATUS)") (class "Default")
      (node (ref "R7") (pin "2") (pinfunction "2_2") (pintype "passive"))
      (node (ref "U1") (pin "F4") (pinfunction "nSTATUS_F4") (pintype "bidirectional"))
    )
    (net (code "190") (name "VCC1.2") (class "Default")
      (node (ref "C1") (pin "2") (pinfunction "2_2") (pintype "passive"))
      (node (ref "C2") (pin "2") (pinfunction "2_2") (pintype "passive"))
      (node (ref "C3") (pin "2") (pinfunction "2_2") (pintype "passive"))
      (node (ref "C4") (pin "2") (pinfunction "2_2") (pintype "passive"))
      (node (ref "C5") (pin "2") (pinfunction "2_2") (pintype "passive"))
      (node (ref "U1") (pin "D13") (pinfunction "VCCD_PLL2_D13") (pintype "power_in"))
      (node (ref "U1") (pin "G10") (pinfunction "VCCINT_G10") (pintype "power_in"))
      (node (ref "U1") (pin "G6") (pinfunction "VCCINT_G6") (pintype "power_in"))
      (node (ref "U1") (pin "G7") (pinfunction "VCCINT_G7") (pintype "power_in"))
      (node (ref "U1") (pin "G8") (pinfunction "VCCINT_G8") (pintype "power_in"))
      (node (ref "U1") (pin "G9") (pinfunction "VCCINT_G9") (pintype "power_in"))
      (node (ref "U1") (pin "H11") (pinfunction "VCCINT_H11") (pintype "power_in"))
      (node (ref "U1") (pin "H6") (pinfunction "VCCINT_H6") (pintype "power_in"))
      (node (ref "U1") (pin "K7") (pinfunction "VCCINT_K7") (pintype "power_in"))
      (node (ref "U1") (pin "N4") (pinfunction "VCCD_PLL1_N4") (pintype "power_in"))
    )
    (net (code "191") (name "VCC2.5") (class "Default")
      (node (ref "C23") (pin "2") (pinfunction "2_2") (pintype "passive"))
      (node (ref "JTAG1") (pin "4") (pinfunction "VCC_4") (pintype "passive"))
      (node (ref "R1") (pin "1") (pinfunction "1_1") (pintype "passive"))
      (node (ref "R3") (pin "1") (pinfunction "1_1") (pintype "passive"))
      (node (ref "U1") (pin "F12") (pinfunction "VCCA2_F12") (pintype "power_in"))
      (node (ref "U1") (pin "H12") (pinfunction "MSEL1_H12") (pintype "input"))
      (node (ref "U1") (pin "L5") (pinfunction "VCCA1_L5") (pintype "power_in"))
    )
    (net (code "192") (name "VCC3.3") (class "Default")
      (node (ref "C10") (pin "2") (pinfunction "2_2") (pintype "passive"))
      (node (ref "C11") (pin "2") (pinfunction "2_2") (pintype "passive"))
      (node (ref "C12") (pin "2") (pinfunction "2_2") (pintype "passive"))
      (node (ref "C13") (pin "2") (pinfunction "2_2") (pintype "passive"))
      (node (ref "C14") (pin "2") (pinfunction "2_2") (pintype "passive"))
      (node (ref "C15") (pin "2") (pinfunction "2_2") (pintype "passive"))
      (node (ref "C16") (pin "2") (pinfunction "2_2") (pintype "passive"))
      (node (ref "C17") (pin "2") (pinfunction "2_2") (pintype "passive"))
      (node (ref "C18") (pin "2") (pinfunction "2_2") (pintype "passive"))
      (node (ref "C19") (pin "2") (pinfunction "2_2") (pintype "passive"))
      (node (ref "C20") (pin "2") (pinfunction "2_2") (pintype "passive"))
      (node (ref "C21") (pin "2") (pinfunction "2_2") (pintype "passive"))
      (node (ref "C22") (pin "2") (pinfunction "2_2") (pintype "passive"))
      (node (ref "C24") (pin "2") (pinfunction "2_2") (pintype "passive"))
      (node (ref "C25") (pin "1") (pinfunction "1_1") (pintype "passive"))
      (node (ref "C6") (pin "2") (pinfunction "2_2") (pintype "passive"))
      (node (ref "C7") (pin "2") (pinfunction "2_2") (pintype "passive"))
      (node (ref "C8") (pin "2") (pinfunction "2_2") (pintype "passive"))
      (node (ref "C9") (pin "2") (pinfunction "2_2") (pintype "passive"))
      (node (ref "R5") (pin "1") (pinfunction "1_1") (pintype "passive"))
      (node (ref "R6") (pin "1") (pinfunction "1_1") (pintype "passive"))
      (node (ref "R7") (pin "1") (pinfunction "1_1") (pintype "passive"))
      (node (ref "U1") (pin "A1") (pinfunction "VCCIO8_A1") (pintype "power_in"))
      (node (ref "U1") (pin "A16") (pinfunction "VCCIO7_A16") (pintype "power_in"))
      (node (ref "U1") (pin "C10") (pinfunction "VCCIO7_C10") (pintype "power_in"))
      (node (ref "U1") (pin "C13") (pinfunction "VCCIO7_C13") (pintype "power_in"))
      (node (ref "U1") (pin "C4") (pinfunction "VCCIO8_C4") (pintype "power_in"))
      (node (ref "U1") (pin "C7") (pinfunction "VCCIO8_C7") (pintype "power_in"))
      (node (ref "U1") (pin "E14") (pinfunction "VCCIO6_E14") (pintype "power_in"))
      (node (ref "U1") (pin "E3") (pinfunction "VCCIO1_E3") (pintype "power_in"))
      (node (ref "U1") (pin "G14") (pinfunction "VCCIO6_G14") (pintype "power_in"))
      (node (ref "U1") (pin "G3") (pinfunction "VCCIO1_G3") (pintype "power_in"))
      (node (ref "U1") (pin "K14") (pinfunction "VCCIO5_K14") (pintype "power_in"))
      (node (ref "U1") (pin "K3") (pinfunction "VCCIO2_K3") (pintype "power_in"))
      (node (ref "U1") (pin "M14") (pinfunction "VCCIO5_M14") (pintype "power_in"))
      (node (ref "U1") (pin "M3") (pinfunction "VCCIO2_M3") (pintype "power_in"))
      (node (ref "U1") (pin "P10") (pinfunction "VCCIO4_P10") (pintype "power_in"))
      (node (ref "U1") (pin "P13") (pinfunction "VCCIO4_P13") (pintype "power_in"))
      (node (ref "U1") (pin "P4") (pinfunction "VCCIO3_P4") (pintype "power_in"))
      (node (ref "U1") (pin "P7") (pinfunction "VCCIO3_P7") (pintype "power_in"))
      (node (ref "U1") (pin "T1") (pinfunction "VCCIO3_T1") (pintype "power_in"))
      (node (ref "U1") (pin "T16") (pinfunction "VCCIO4_T16") (pintype "power_in"))
      (node (ref "U2") (pin "3") (pinfunction "~{W}_3") (pintype "input"))
      (node (ref "U2") (pin "7") (pinfunction "~{HOLD}_7") (pintype "input"))
      (node (ref "U2") (pin "8") (pinfunction "VCC_8") (pintype "power_in"))
      (node (ref "X1") (pin "4") (pinfunction "VCC_4") (pintype "passive"))
    )
    (net (code "193") (name "unconnected-(JTAG1-NC-Pad6)") (class "Default")
      (node (ref "JTAG1") (pin "6") (pinfunction "NC_6") (pintype "passive+no_connect"))
    )
    (net (code "194") (name "unconnected-(JTAG1-NC-Pad7)") (class "Default")
      (node (ref "JTAG1") (pin "7") (pinfunction "NC_7") (pintype "passive+no_connect"))
    )
    (net (code "195") (name "unconnected-(JTAG1-NC-Pad8)") (class "Default")
      (node (ref "JTAG1") (pin "8") (pinfunction "NC_8") (pintype "passive+no_connect"))
    )
    (net (code "196") (name "unconnected-(X1-EN{slash}NC-Pad1)") (class "Default")
      (node (ref "X1") (pin "1") (pinfunction "EN/NC_1") (pintype "passive"))
    )
  )
)
